# 2020-04-02-04-30101_-_ETC_Interface_Circ.net
KiCad netlist of a schematic drawn in Altium Designer
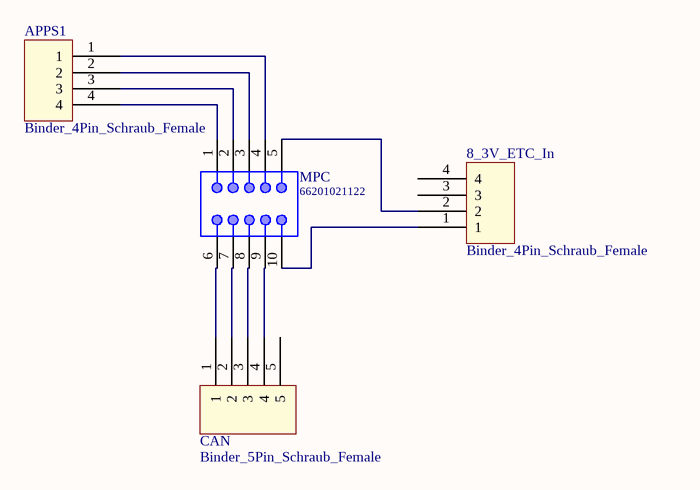
[diagram p0: 2020-04-02-04-30101 - ETC_Interface_Circuit_1.SchDoc]

(export (version "E")
  (design (tool "Eeschema 10.0.6"))
  (components
    (comp (ref "8_3V_ETC_In")
      (value "Binder_4Pin_Schraub_Female")
      (footprint "09 0412 30 04")
      (libsource (lib "Eric") (part "Binder_4Pin_Schraub_Female"))
    )
    (comp (ref "APPS1")
      (value "Binder_4Pin_Schraub_Female")
      (footprint "09 0412 30 04")
      (libsource (lib "") (part "Binder_4Pin_Schraub_Female_1"))
    )
    (comp (ref "CAN")
      (value "Binder_5Pin_Schraub_Female")
      (footprint "09 0416 30 05")
      (libsource (lib "Eric") (part "Binder_5Pin_Schraub_Female"))
    )
    (comp (ref "MPC")
      (value "66201021122")
      (footprint "66201021122")
      (description "THT Male Header WR-MPC3, Vertical, Dual Row, pitch 3 mm, 10 pins")
      (fields (field (name "PUBLISHER") "Wurth Elektronik"))
      (libsource (lib "66202421122_Altium_WR-MPC3_rev18b") (part "66201021122"))
    )
  )
  (nets
    (net (code "1") (name "Net-(8_3V_ETC_In-Pad1)") (class "Default")
      (node (ref "8_3V_ETC_In") (pin "1") (pinfunction "1_1") (pintype "passive"))
      (node (ref "MPC") (pin "10") (pinfunction "10_10") (pintype "passive"))
    )
    (net (code "2") (name "Net-(8_3V_ETC_In-Pad2)") (class "Default")
      (node (ref "8_3V_ETC_In") (pin "2") (pinfunction "2_2") (pintype "passive"))
      (node (ref "MPC") (pin "5") (pinfunction "5_5") (pintype "passive"))
    )
    (net (code "3") (name "Net-(APPS1-Pad1)") (class "Default")
      (node (ref "APPS1") (pin "1") (pinfunction "1_1") (pintype "passive"))
      (node (ref "MPC") (pin "4") (pinfunction "4_4") (pintype "passive"))
    )
    (net (code "4") (name "Net-(APPS1-Pad2)") (class "Default")
      (node (ref "APPS1") (pin "2") (pinfunction "2_2") (pintype "passive"))
      (node (ref "MPC") (pin "3") (pinfunction "3_3") (pintype "passive"))
    )
    (net (code "5") (name "Net-(APPS1-Pad3)") (class "Default")
      (node (ref "APPS1") (pin "3") (pinfunction "3_3") (pintype "passive"))
      (node (ref "MPC") (pin "2") (pinfunction "2_2") (pintype "passive"))
    )
    (net (code "6") (name "Net-(APPS1-Pad4)") (class "Default")
      (node (ref "APPS1") (pin "4") (pinfunction "4_4") (pintype "passive"))
      (node (ref "MPC") (pin "1") (pinfunction "1_1") (pintype "passive"))
    )
    (net (code "7") (name "Net-(CAN-Pad1)") (class "Default")
      (node (ref "CAN") (pin "1") (pinfunction "1_1") (pintype "passive"))
      (node (ref "MPC") (pin "6") (pinfunction "6_6") (pintype "passive"))
    )
    (net (code "8") (name "Net-(CAN-Pad2)") (class "Default")
      (node (ref "CAN") (pin "2") (pinfunction "2_2") (pintype "passive"))
      (node (ref "MPC") (pin "7") (pinfunction "7_7") (pintype "passive"))
    )
    (net (code "9") (name "Net-(CAN-Pad3)") (class "Default")
      (node (ref "CAN") (pin "3") (pinfunction "3_3") (pintype "passive"))
      (node (ref "MPC") (pin "8") (pinfunction "8_8") (pintype "passive"))
    )
    (net (code "10") (name "Net-(CAN-Pad4)") (class "Default")
      (node (ref "CAN") (pin "4") (pinfunction "4_4") (pintype "passive"))
      (node (ref "MPC") (pin "9") (pinfunction "9_9") (pintype "passive"))
    )
    (net (code "11") (name "unconnected-(8_3V_ETC_In-Pad3)") (class "Default")
      (node (ref "8_3V_ETC_In") (pin "3") (pinfunction "3_3") (pintype "passive"))
    )
    (net (code "12") (name "unconnected-(8_3V_ETC_In-Pad4)") (class "Default")
      (node (ref "8_3V_ETC_In") (pin "4") (pinfunction "4_4") (pintype "passive"))
    )
    (net (code "13") (name "unconnected-(CAN-Pad5)") (class "Default")
      (node (ref "CAN") (pin "5") (pinfunction "5_5") (pintype "passive"))
    )
  )
)
